# color-detector.net
KiCad netlist of a schematic drawn in EAGLE
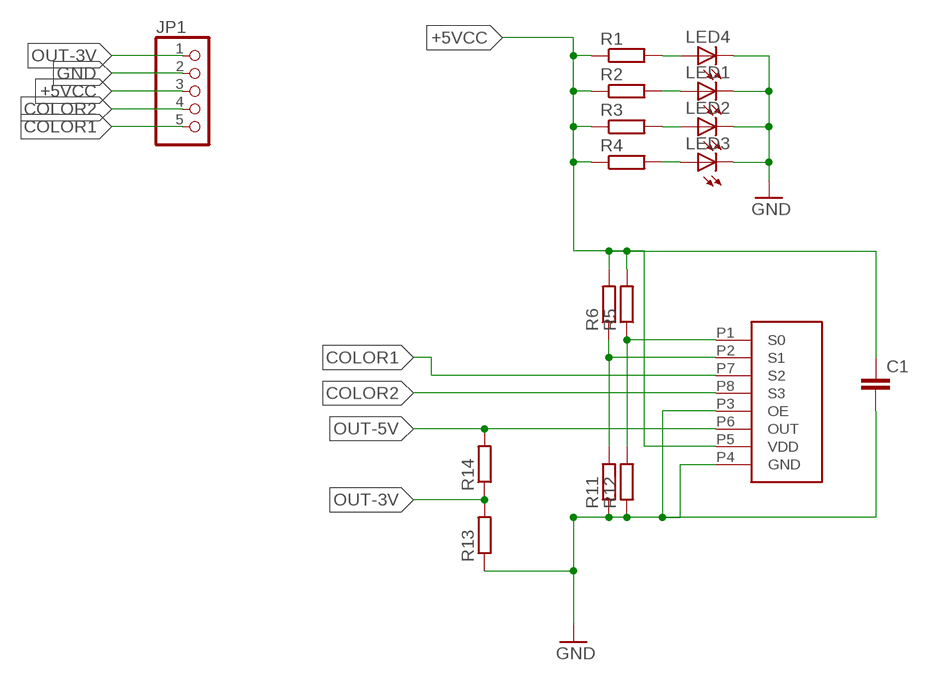
[diagram p0: schematic, sheet 1]

(export (version "E")
  (design (tool "Eeschema 10.0.6"))
  (components
    (comp (ref "C1")
      (value "C-EUC0805")
      (footprint "eagle-import:C0805")
      (libsource (lib "eagle-import") (part "C-EUC0805"))
    )
    (comp (ref "JP1")
      (value "PINHD-1X5/90")
      (footprint "eagle-import:1X05_90")
      (libsource (lib "eagle-import") (part "PINHD-1X5/90"))
    )
    (comp (ref "LED1")
      (value "LED3MM")
      (footprint "eagle-import:LED3MM")
      (libsource (lib "eagle-import") (part "LED3MM"))
    )
    (comp (ref "LED2")
      (value "LED3MM")
      (footprint "eagle-import:LED3MM")
      (libsource (lib "eagle-import") (part "LED3MM"))
    )
    (comp (ref "LED3")
      (value "LED3MM")
      (footprint "eagle-import:LED3MM")
      (libsource (lib "eagle-import") (part "LED3MM"))
    )
    (comp (ref "LED4")
      (value "LED3MM")
      (footprint "eagle-import:LED3MM")
      (libsource (lib "eagle-import") (part "LED3MM"))
    )
    (comp (ref "R1")
      (value "R-EU_R0805")
      (footprint "eagle-import:R0805")
      (libsource (lib "eagle-import") (part "R-EU_R0805"))
    )
    (comp (ref "R2")
      (value "R-EU_R0805")
      (footprint "eagle-import:R0805")
      (libsource (lib "eagle-import") (part "R-EU_R0805"))
    )
    (comp (ref "R3")
      (value "R-EU_R0805")
      (footprint "eagle-import:R0805")
      (libsource (lib "eagle-import") (part "R-EU_R0805"))
    )
    (comp (ref "R4")
      (value "R-EU_R0805")
      (footprint "eagle-import:R0805")
      (libsource (lib "eagle-import") (part "R-EU_R0805"))
    )
    (comp (ref "R5")
      (value "R-EU_R0402")
      (footprint "eagle-import:R0402")
      (libsource (lib "eagle-import") (part "R-EU_R0402"))
    )
    (comp (ref "R6")
      (value "R-EU_R0402")
      (footprint "eagle-import:R0402")
      (libsource (lib "eagle-import") (part "R-EU_R0402"))
    )
    (comp (ref "R11")
      (value "R-EU_R0402")
      (footprint "eagle-import:R0402")
      (libsource (lib "eagle-import") (part "R-EU_R0402"))
    )
    (comp (ref "R12")
      (value "R-EU_R0402")
      (footprint "eagle-import:R0402")
      (libsource (lib "eagle-import") (part "R-EU_R0402"))
    )
    (comp (ref "R13")
      (value "R-EU_R0805")
      (footprint "eagle-import:R0805")
      (libsource (lib "eagle-import") (part "R-EU_R0805"))
    )
    (comp (ref "R14")
      (value "R-EU_R0805")
      (footprint "eagle-import:R0805")
      (libsource (lib "eagle-import") (part "R-EU_R0805"))
    )
    (comp (ref "U$1")
      (value "TCS3200")
      (footprint "eagle-import:SOIC8")
      (libsource (lib "eagle-import") (part "TCS3200"))
    )
  )
  (nets
    (net (code "1") (name "+5VCC") (class "Default")
      (node (ref "C1") (pin "1") (pinfunction "1_1") (pintype "passive"))
      (node (ref "JP1") (pin "3") (pinfunction "3_3") (pintype "passive"))
      (node (ref "R1") (pin "1") (pinfunction "1_1") (pintype "passive"))
      (node (ref "R2") (pin "1") (pinfunction "1_1") (pintype "passive"))
      (node (ref "R3") (pin "1") (pinfunction "1_1") (pintype "passive"))
      (node (ref "R4") (pin "1") (pinfunction "1_1") (pintype "passive"))
      (node (ref "R5") (pin "2") (pinfunction "2_2") (pintype "passive"))
      (node (ref "R6") (pin "2") (pinfunction "2_2") (pintype "passive"))
      (node (ref "U$1") (pin "P5") (pinfunction "VDD_P5") (pintype "bidirectional"))
    )
    (net (code "2") (name "COLOR1") (class "Default")
      (node (ref "JP1") (pin "5") (pinfunction "5_5") (pintype "passive"))
      (node (ref "U$1") (pin "P7") (pinfunction "S2_P7") (pintype "bidirectional"))
    )
    (net (code "3") (name "COLOR2") (class "Default")
      (node (ref "JP1") (pin "4") (pinfunction "4_4") (pintype "passive"))
      (node (ref "U$1") (pin "P8") (pinfunction "S3_P8") (pintype "bidirectional"))
    )
    (net (code "4") (name "GND") (class "Default")
      (node (ref "C1") (pin "2") (pinfunction "2_2") (pintype "passive"))
      (node (ref "JP1") (pin "2") (pinfunction "2_2") (pintype "passive"))
      (node (ref "LED1") (pin "K") (pinfunction "C_K") (pintype "passive"))
      (node (ref "LED2") (pin "K") (pinfunction "C_K") (pintype "passive"))
      (node (ref "LED3") (pin "K") (pinfunction "C_K") (pintype "passive"))
      (node (ref "LED4") (pin "K") (pinfunction "C_K") (pintype "passive"))
      (node (ref "R11") (pin "1") (pinfunction "1_1") (pintype "passive"))
      (node (ref "R12") (pin "1") (pinfunction "1_1") (pintype "passive"))
      (node (ref "R13") (pin "1") (pinfunction "1_1") (pintype "passive"))
      (node (ref "U$1") (pin "P3") (pinfunction "OE_P3") (pintype "bidirectional"))
      (node (ref "U$1") (pin "P4") (pinfunction "GND_P4") (pintype "bidirectional"))
    )
    (net (code "5") (name "Net-(LED1-PadA)") (class "Default")
      (node (ref "LED1") (pin "A") (pinfunction "A_A") (pintype "passive"))
      (node (ref "R2") (pin "2") (pinfunction "2_2") (pintype "passive"))
    )
    (net (code "6") (name "Net-(LED2-PadA)") (class "Default")
      (node (ref "LED2") (pin "A") (pinfunction "A_A") (pintype "passive"))
      (node (ref "R3") (pin "2") (pinfunction "2_2") (pintype "passive"))
    )
    (net (code "7") (name "Net-(LED3-PadA)") (class "Default")
      (node (ref "LED3") (pin "A") (pinfunction "A_A") (pintype "passive"))
      (node (ref "R4") (pin "2") (pinfunction "2_2") (pintype "passive"))
    )
    (net (code "8") (name "Net-(LED4-PadA)") (class "Default")
      (node (ref "LED4") (pin "A") (pinfunction "A_A") (pintype "passive"))
      (node (ref "R1") (pin "2") (pinfunction "2_2") (pintype "passive"))
    )
    (net (code "9") (name "Net-(U$1-S0)") (class "Default")
      (node (ref "R12") (pin "2") (pinfunction "2_2") (pintype "passive"))
      (node (ref "R5") (pin "1") (pinfunction "1_1") (pintype "passive"))
      (node (ref "U$1") (pin "P1") (pinfunction "S0_P1") (pintype "bidirectional"))
    )
    (net (code "10") (name "Net-(U$1-S1)") (class "Default")
      (node (ref "R11") (pin "2") (pinfunction "2_2") (pintype "passive"))
      (node (ref "R6") (pin "1") (pinfunction "1_1") (pintype "passive"))
      (node (ref "U$1") (pin "P2") (pinfunction "S1_P2") (pintype "bidirectional"))
    )
    (net (code "11") (name "OUT-3V") (class "Default")
      (node (ref "JP1") (pin "1") (pinfunction "1_1") (pintype "passive"))
      (node (ref "R13") (pin "2") (pinfunction "2_2") (pintype "passive"))
      (node (ref "R14") (pin "1") (pinfunction "1_1") (pintype "passive"))
    )
    (net (code "12") (name "OUT-5V") (class "Default")
      (node (ref "R14") (pin "2") (pinfunction "2_2") (pintype "passive"))
      (node (ref "U$1") (pin "P6") (pinfunction "OUT_P6") (pintype "bidirectional"))
    )
  )
)
